# Safety_2019_V_3_0_RTDS.net
KiCad netlist of a schematic drawn in Altium Designer
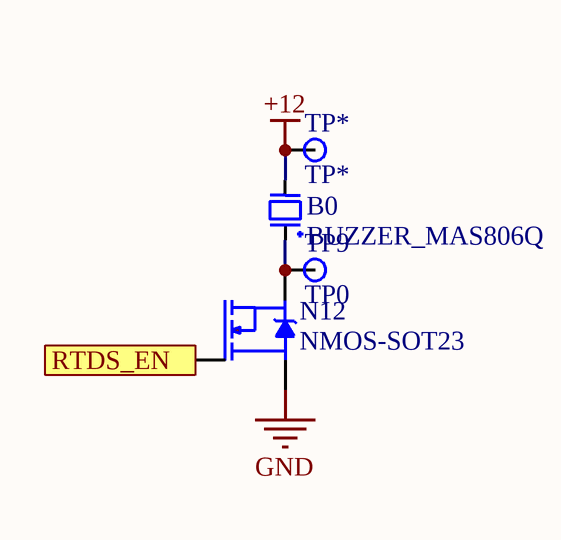
[diagram p0: Safety_2019_V_3_0_RTDS.SchDoc]

(export (version "E")
  (design (tool "Eeschema 10.0.6"))
  (components
    (comp (ref "B0")
      (value "BUZZER_MAS806Q")
      (footprint "BUZZER_MAS806Q")
      (libsource (lib "ife19_Elec_Library") (part "BUZZER_MAS806Q"))
    )
    (comp (ref "N12")
      (value "NMOS-SOT23")
      (footprint "SOT23")
      (libsource (lib "ife19_Elec_Library") (part "NMOS-SOT23"))
    )
    (comp (ref "TP*")
      (value "TP*")
      (footprint "Testpoint")
      (libsource (lib "ife19_Elec_Library") (part "Testpoint"))
    )
    (comp (ref "TP9")
      (value "TP0")
      (footprint "Testpoint")
      (libsource (lib "ife19_Elec_Library") (part "Testpoint"))
    )
  )
  (nets
    (net (code "1") (name "+12") (class "Default")
      (node (ref "B0") (pin "-") (pinfunction "-_-") (pintype "passive"))
      (node (ref "TP*") (pin "1") (pinfunction "1_1") (pintype "passive"))
    )
    (net (code "2") (name "/RTDS_EN") (class "Default")
      (node (ref "N12") (pin "1") (pinfunction "G_1") (pintype "passive"))
    )
    (net (code "3") (name "GND") (class "Default")
      (node (ref "N12") (pin "2") (pinfunction "S_2") (pintype "passive"))
    )
    (net (code "4") (name "Net-(N12-D)") (class "Default")
      (node (ref "B0") (pin "+") (pinfunction "+_+") (pintype "passive"))
      (node (ref "N12") (pin "3") (pinfunction "D_3") (pintype "passive"))
      (node (ref "TP9") (pin "1") (pinfunction "1_1") (pintype "passive"))
    )
  )
)
